# DAC.net
KiCad netlist of a schematic drawn in Altium Designer
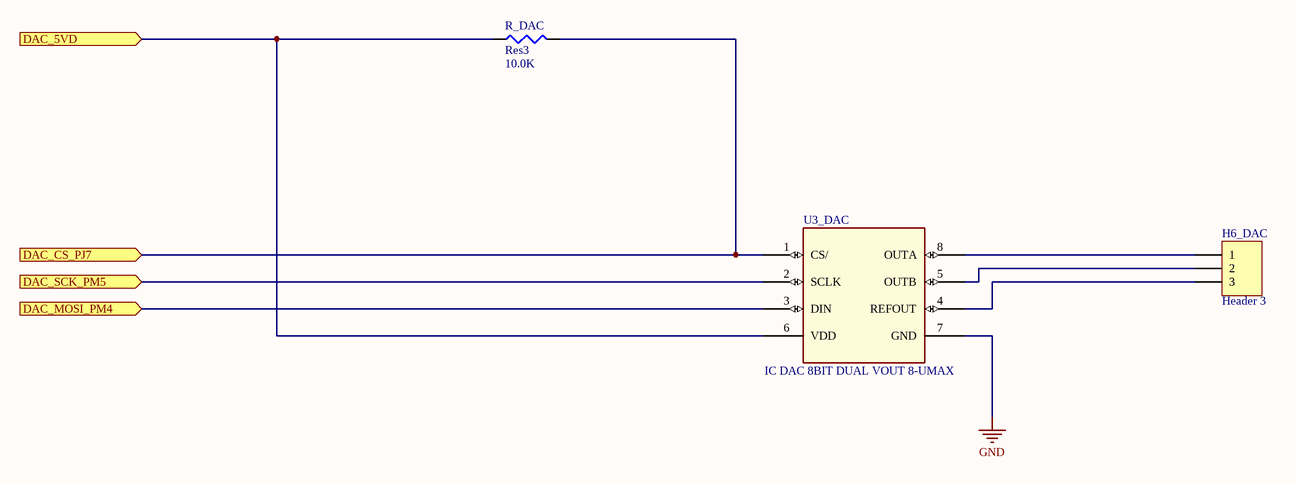
[diagram p0: DAC.SchDoc]

(export (version "E")
  (design (tool "Eeschema 10.0.6"))
  (components
    (comp (ref "H6_DAC")
      (value "Header 3")
      (footprint "HDR1X3")
      (description "Header, 3-Pin")
      (fields (field (name "PUBLISHER") "Altium Limited"))
      (libsource (lib "Miscellaneous Connectors") (part "Header 3"))
    )
    (comp (ref "R_DAC")
      (value "Res3")
      (footprint "RESC2112X05M")
      (description "RES SMD 10.0K OHM 1% 1/8W 0805")
      (fields (field (name "ALTIUM_VALUE") "10.0K") (field (name "MPN") "CRCW080510K0FKEA"))
      (libsource (lib "esd_library") (part "Resistor_10.0K"))
    )
    (comp (ref "U3_DAC")
      (value "IC DAC 8BIT DUAL VOUT 8-UMAX")
      (footprint "TSOP65P490X110-8M")
      (fields (field (name "MPN") "MAX5513EUA+"))
      (libsource (lib "esd_library") (part "Max5513-dac"))
    )
  )
  (nets
    (net (code "1") (name "/DAC_5VD") (class "Default")
      (node (ref "R_DAC") (pin "1") (pinfunction "1_1") (pintype "passive"))
      (node (ref "U3_DAC") (pin "6") (pinfunction "VDD_6") (pintype "power_in"))
    )
    (net (code "2") (name "/DAC_CS_PJ7") (class "Default")
      (node (ref "R_DAC") (pin "2") (pinfunction "2_2") (pintype "passive"))
      (node (ref "U3_DAC") (pin "1") (pinfunction "CS/_1") (pintype "bidirectional"))
    )
    (net (code "3") (name "/DAC_MOSI_PM4") (class "Default")
      (node (ref "U3_DAC") (pin "3") (pinfunction "DIN_3") (pintype "bidirectional"))
    )
    (net (code "4") (name "/DAC_SCK_PM5") (class "Default")
      (node (ref "U3_DAC") (pin "2") (pinfunction "SCLK_2") (pintype "bidirectional"))
    )
    (net (code "5") (name "GND") (class "Default")
      (node (ref "U3_DAC") (pin "7") (pinfunction "GND_7") (pintype "power_in"))
    )
    (net (code "6") (name "Net-(U3_DAC-OUTA)") (class "Default")
      (node (ref "H6_DAC") (pin "1") (pinfunction "1_1") (pintype "passive"))
      (node (ref "U3_DAC") (pin "8") (pinfunction "OUTA_8") (pintype "bidirectional"))
    )
    (net (code "7") (name "Net-(U3_DAC-OUTB)") (class "Default")
      (node (ref "H6_DAC") (pin "2") (pinfunction "2_2") (pintype "passive"))
      (node (ref "U3_DAC") (pin "5") (pinfunction "OUTB_5") (pintype "bidirectional"))
    )
    (net (code "8") (name "Net-(U3_DAC-REFOUT)") (class "Default")
      (node (ref "H6_DAC") (pin "3") (pinfunction "3_3") (pintype "passive"))
      (node (ref "U3_DAC") (pin "4") (pinfunction "REFOUT_4") (pintype "bidirectional"))
    )
  )
)
